# Main-v3_0.net
KiCad netlist of a schematic drawn in EAGLE
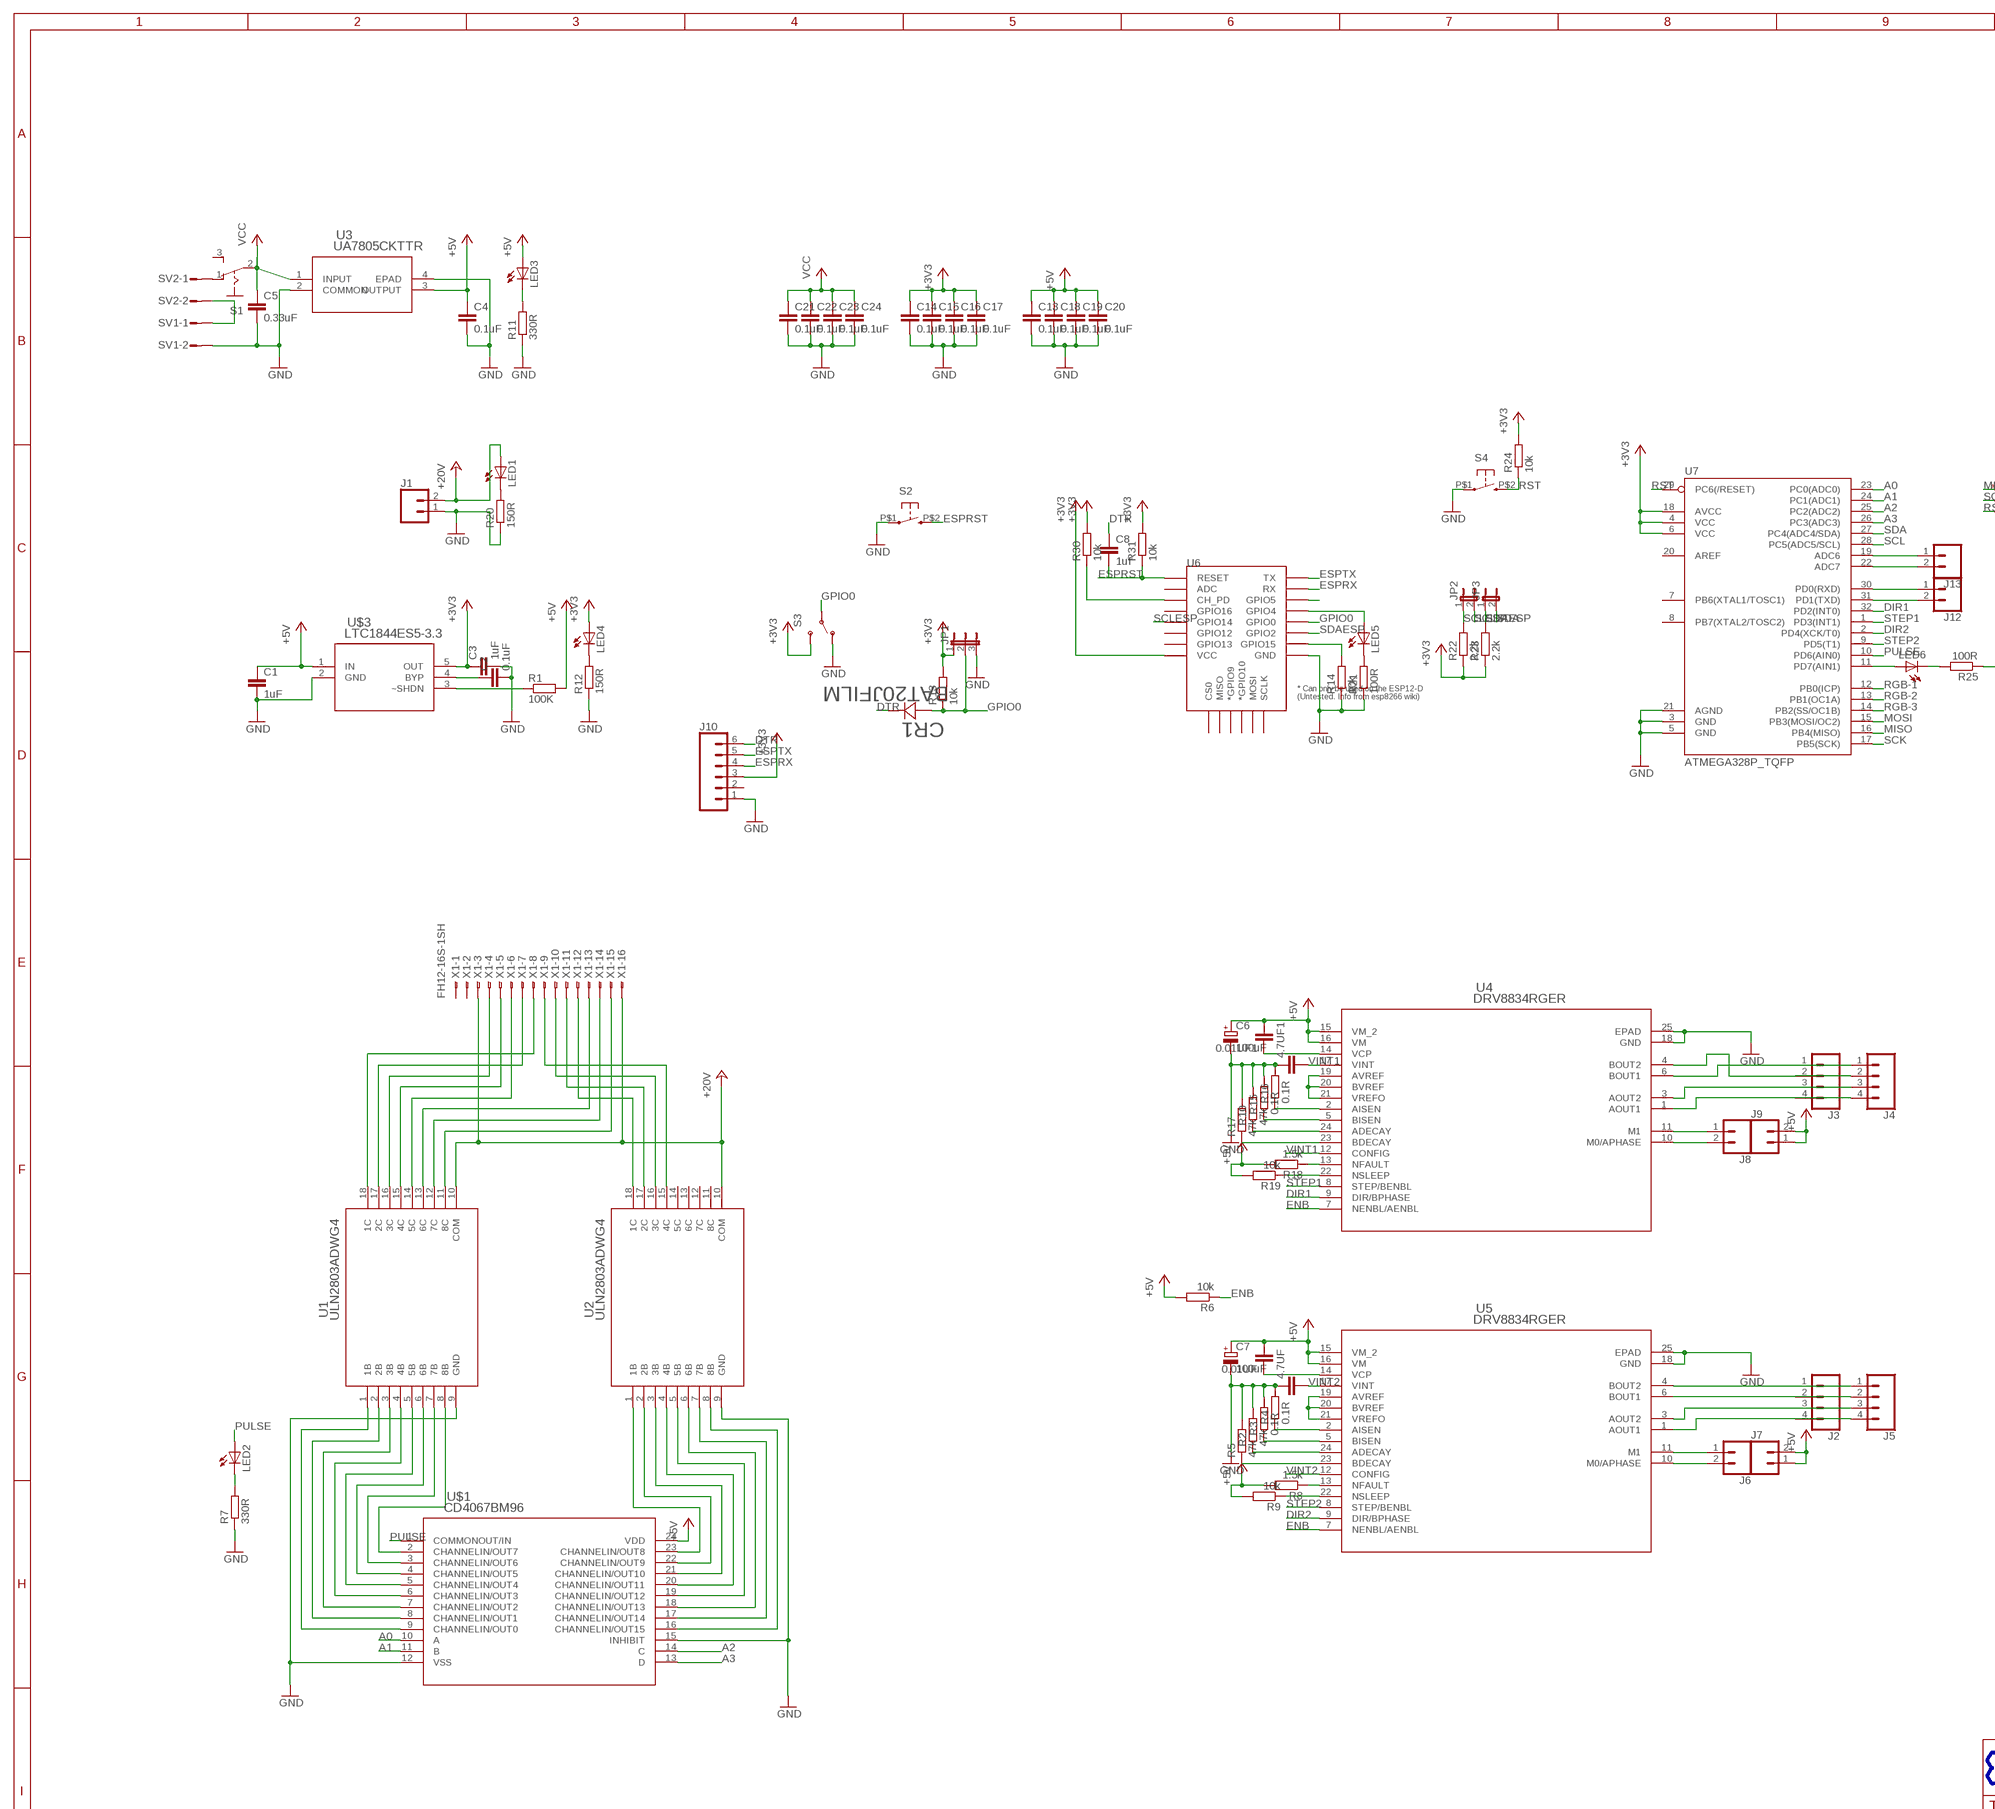
[diagram p0: schematic, sheet 1, part 1 of 2]
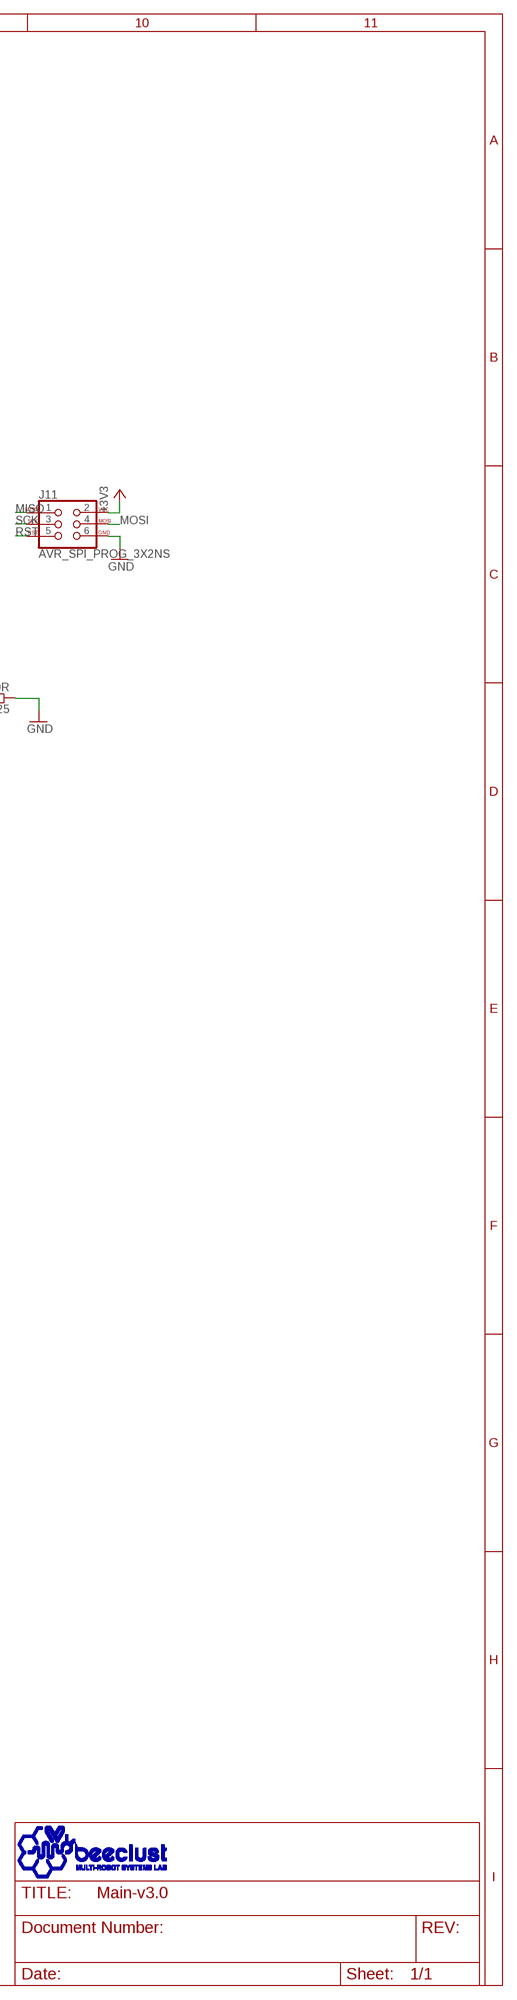
[diagram p1: schematic, sheet 1, part 2 of 2]

(export (version "E")
  (design (tool "Eeschema 10.0.6"))
  (components
    (comp (ref "0.01UF")
      (value "C-EUC0603K")
      (footprint "eagle-import:C0603K")
      (libsource (lib "eagle-import") (part "resistor_348_C-EUC0603K"))
    )
    (comp (ref "0.01UF1")
      (value "C-EUC0603K")
      (footprint "eagle-import:C0603K")
      (libsource (lib "eagle-import") (part "resistor_348_C-EUC0603K"))
    )
    (comp (ref "4.7UF")
      (value "C-EUC0603K")
      (footprint "eagle-import:C0603K")
      (libsource (lib "eagle-import") (part "resistor_348_C-EUC0603K"))
    )
    (comp (ref "4.7UF1")
      (value "C-EUC0603K")
      (footprint "eagle-import:C0603K")
      (libsource (lib "eagle-import") (part "resistor_348_C-EUC0603K"))
    )
    (comp (ref "C1")
      (value "1uF")
      (footprint "eagle-import:C0603")
      (libsource (lib "eagle-import") (part "C-EUC0603"))
    )
    (comp (ref "C2")
      (value "0.1uF")
      (footprint "eagle-import:C0603")
      (libsource (lib "eagle-import") (part "C-EUC0603"))
    )
    (comp (ref "C3")
      (value "1uF")
      (footprint "eagle-import:C0603")
      (libsource (lib "eagle-import") (part "C-EUC0603"))
    )
    (comp (ref "C4")
      (value "0.1uF")
      (footprint "eagle-import:C0603")
      (libsource (lib "eagle-import") (part "C-EUC0603"))
    )
    (comp (ref "C5")
      (value "0.33uF")
      (footprint "eagle-import:C0603")
      (libsource (lib "eagle-import") (part "C-EUC0603"))
    )
    (comp (ref "C6")
      (value "100uF")
      (footprint "eagle-import:E5-5")
      (libsource (lib "eagle-import") (part "CPOL-EUE5-5"))
    )
    (comp (ref "C7")
      (value "100uF")
      (footprint "eagle-import:E5-5")
      (libsource (lib "eagle-import") (part "CPOL-EUE5-5"))
    )
    (comp (ref "C8")
      (value "1uf")
      (footprint "eagle-import:C0603")
      (libsource (lib "eagle-import") (part "resistor_348_C-EUC0603"))
    )
    (comp (ref "C13")
      (value "0.1uF")
      (footprint "eagle-import:C0603")
      (libsource (lib "eagle-import") (part "C-EUC0603"))
    )
    (comp (ref "C14")
      (value "0.1uF")
      (footprint "eagle-import:C0603")
      (libsource (lib "eagle-import") (part "C-EUC0603"))
    )
    (comp (ref "C15")
      (value "0.1uF")
      (footprint "eagle-import:C0603")
      (libsource (lib "eagle-import") (part "C-EUC0603"))
    )
    (comp (ref "C16")
      (value "0.1uF")
      (footprint "eagle-import:C0603")
      (libsource (lib "eagle-import") (part "C-EUC0603"))
    )
    (comp (ref "C17")
      (value "0.1uF")
      (footprint "eagle-import:C0603")
      (libsource (lib "eagle-import") (part "C-EUC0603"))
    )
    (comp (ref "C18")
      (value "0.1uF")
      (footprint "eagle-import:C0603")
      (libsource (lib "eagle-import") (part "C-EUC0603"))
    )
    (comp (ref "C19")
      (value "0.1uF")
      (footprint "eagle-import:C0603")
      (libsource (lib "eagle-import") (part "C-EUC0603"))
    )
    (comp (ref "C20")
      (value "0.1uF")
      (footprint "eagle-import:C0603")
      (libsource (lib "eagle-import") (part "C-EUC0603"))
    )
    (comp (ref "C21")
      (value "0.1uF")
      (footprint "eagle-import:C0603")
      (libsource (lib "eagle-import") (part "C-EUC0603"))
    )
    (comp (ref "C22")
      (value "0.1uF")
      (footprint "eagle-import:C0603")
      (libsource (lib "eagle-import") (part "C-EUC0603"))
    )
    (comp (ref "C23")
      (value "0.1uF")
      (footprint "eagle-import:C0603")
      (libsource (lib "eagle-import") (part "C-EUC0603"))
    )
    (comp (ref "C24")
      (value "0.1uF")
      (footprint "eagle-import:C0603")
      (libsource (lib "eagle-import") (part "C-EUC0603"))
    )
    (comp (ref "CR1")
      (value "BAT20JFILM")
      (footprint "eagle-import:SOD-323")
      (libsource (lib "eagle-import") (part "BAT20JFILM"))
    )
    (comp (ref "J1")
      (value "CONN_02")
      (footprint "eagle-import:1X02")
      (libsource (lib "eagle-import") (part "CONN_02"))
    )
    (comp (ref "J2")
      (value "CONN_04")
      (footprint "eagle-import:1X04")
      (libsource (lib "eagle-import") (part "CONN_04"))
    )
    (comp (ref "J3")
      (value "CONN_04")
      (footprint "eagle-import:1X04")
      (libsource (lib "eagle-import") (part "CONN_04"))
    )
    (comp (ref "J4")
      (value "CONN_04")
      (footprint "eagle-import:1X04")
      (libsource (lib "eagle-import") (part "CONN_04"))
    )
    (comp (ref "J5")
      (value "CONN_04")
      (footprint "eagle-import:1X04")
      (libsource (lib "eagle-import") (part "CONN_04"))
    )
    (comp (ref "J6")
      (value "CONN_02")
      (footprint "eagle-import:1X02")
      (libsource (lib "eagle-import") (part "CONN_02"))
    )
    (comp (ref "J7")
      (value "CONN_02")
      (footprint "eagle-import:1X02")
      (libsource (lib "eagle-import") (part "CONN_02"))
    )
    (comp (ref "J8")
      (value "CONN_02")
      (footprint "eagle-import:1X02")
      (libsource (lib "eagle-import") (part "CONN_02"))
    )
    (comp (ref "J9")
      (value "CONN_02")
      (footprint "eagle-import:1X02")
      (libsource (lib "eagle-import") (part "CONN_02"))
    )
    (comp (ref "J10")
      (value "CONN_06NO_SILK_NO_POP")
      (footprint "eagle-import:1X06_NO_SILK")
      (libsource (lib "eagle-import") (part "CONN_06NO_SILK_NO_POP"))
    )
    (comp (ref "J11")
      (value "AVR_SPI_PROG_3X2NS")
      (footprint "eagle-import:2X3-NS")
      (libsource (lib "eagle-import") (part "AVR_SPI_PROG_3X2NS"))
    )
    (comp (ref "J12")
      (value "CONN_02")
      (footprint "eagle-import:1X02")
      (libsource (lib "eagle-import") (part "CONN_02"))
    )
    (comp (ref "J13")
      (value "CONN_02")
      (footprint "eagle-import:1X02")
      (libsource (lib "eagle-import") (part "CONN_02"))
    )
    (comp (ref "JP1")
      (value "JP2E")
      (footprint "eagle-import:JP2")
      (libsource (lib "eagle-import") (part "JP2E"))
    )
    (comp (ref "JP2")
      (value "JP1E")
      (footprint "eagle-import:JP1")
      (libsource (lib "eagle-import") (part "JP1E"))
    )
    (comp (ref "JP3")
      (value "JP1E")
      (footprint "eagle-import:JP1")
      (libsource (lib "eagle-import") (part "JP1E"))
    )
    (comp (ref "LED1")
      (value "LEDSML0603")
      (footprint "eagle-import:SML0603")
      (libsource (lib "eagle-import") (part "LEDSML0603"))
    )
    (comp (ref "LED2")
      (value "LEDSML0603")
      (footprint "eagle-import:SML0603")
      (libsource (lib "eagle-import") (part "LEDSML0603"))
    )
    (comp (ref "LED3")
      (value "LEDSML0603")
      (footprint "eagle-import:SML0603")
      (libsource (lib "eagle-import") (part "LEDSML0603"))
    )
    (comp (ref "LED4")
      (value "LEDSML0603")
      (footprint "eagle-import:SML0603")
      (libsource (lib "eagle-import") (part "LEDSML0603"))
    )
    (comp (ref "LED5")
      (value "LEDSML0603")
      (footprint "eagle-import:SML0603")
      (libsource (lib "eagle-import") (part "LEDSML0603"))
    )
    (comp (ref "LED6")
      (value "LEDSML0603")
      (footprint "eagle-import:SML0603")
      (libsource (lib "eagle-import") (part "LEDSML0603"))
    )
    (comp (ref "R1")
      (value "100K")
      (footprint "eagle-import:R0603")
      (libsource (lib "eagle-import") (part "R-EU_R0603"))
    )
    (comp (ref "R2")
      (value "47k")
      (footprint "eagle-import:R0402")
      (libsource (lib "eagle-import") (part "resistor_348_R-EU_R0402"))
    )
    (comp (ref "R3")
      (value "0.1R")
      (footprint "eagle-import:R0402")
      (libsource (lib "eagle-import") (part "resistor_348_R-EU_R0402"))
    )
    (comp (ref "R4")
      (value "0.1R")
      (footprint "eagle-import:R0402")
      (libsource (lib "eagle-import") (part "resistor_348_R-EU_R0402"))
    )
    (comp (ref "R5")
      (value "47k")
      (footprint "eagle-import:R0402")
      (libsource (lib "eagle-import") (part "resistor_348_R-EU_R0402"))
    )
    (comp (ref "R6")
      (value "10k")
      (footprint "eagle-import:R0402")
      (libsource (lib "eagle-import") (part "resistor_348_R-EU_R0402"))
    )
    (comp (ref "R7")
      (value "330R")
      (footprint "eagle-import:R0603")
      (libsource (lib "eagle-import") (part "R-EU_R0603"))
    )
    (comp (ref "R8")
      (value "1.5k")
      (footprint "eagle-import:R0402")
      (libsource (lib "eagle-import") (part "resistor_348_R-EU_R0402"))
    )
    (comp (ref "R9")
      (value "10k")
      (footprint "eagle-import:R0402")
      (libsource (lib "eagle-import") (part "resistor_348_R-EU_R0402"))
    )
    (comp (ref "R10")
      (value "47k")
      (footprint "eagle-import:R0402")
      (libsource (lib "eagle-import") (part "resistor_348_R-EU_R0402"))
    )
    (comp (ref "R11")
      (value "330R")
      (footprint "eagle-import:R0603")
      (libsource (lib "eagle-import") (part "R-EU_R0603"))
    )
    (comp (ref "R12")
      (value "150R")
      (footprint "eagle-import:R0603")
      (libsource (lib "eagle-import") (part "R-EU_R0603"))
    )
    (comp (ref "R13")
      (value "10k")
      (footprint "eagle-import:R0603")
      (libsource (lib "eagle-import") (part "R-EU_R0603"))
    )
    (comp (ref "R14")
      (value "10k")
      (footprint "eagle-import:R0603")
      (libsource (lib "eagle-import") (part "R-EU_R0603"))
    )
    (comp (ref "R15")
      (value "0.1R")
      (footprint "eagle-import:R0402")
      (libsource (lib "eagle-import") (part "resistor_348_R-EU_R0402"))
    )
    (comp (ref "R16")
      (value "0.1R")
      (footprint "eagle-import:R0402")
      (libsource (lib "eagle-import") (part "resistor_348_R-EU_R0402"))
    )
    (comp (ref "R17")
      (value "47k")
      (footprint "eagle-import:R0402")
      (libsource (lib "eagle-import") (part "resistor_348_R-EU_R0402"))
    )
    (comp (ref "R18")
      (value "1.5k")
      (footprint "eagle-import:R0402")
      (libsource (lib "eagle-import") (part "resistor_348_R-EU_R0402"))
    )
    (comp (ref "R19")
      (value "10k")
      (footprint "eagle-import:R0402")
      (libsource (lib "eagle-import") (part "resistor_348_R-EU_R0402"))
    )
    (comp (ref "R20")
      (value "150R")
      (footprint "eagle-import:R0603")
      (libsource (lib "eagle-import") (part "R-EU_R0603"))
    )
    (comp (ref "R21")
      (value "100R")
      (footprint "eagle-import:R0603")
      (libsource (lib "eagle-import") (part "R-EU_R0603"))
    )
    (comp (ref "R22")
      (value "2.2k")
      (footprint "eagle-import:R0603")
      (libsource (lib "eagle-import") (part "R-EU_R0603"))
    )
    (comp (ref "R23")
      (value "2.2k")
      (footprint "eagle-import:R0603")
      (libsource (lib "eagle-import") (part "R-EU_R0603"))
    )
    (comp (ref "R24")
      (value "10k")
      (footprint "eagle-import:R0603")
      (libsource (lib "eagle-import") (part "R-EU_R0603"))
    )
    (comp (ref "R25")
      (value "100R")
      (footprint "eagle-import:R0603")
      (libsource (lib "eagle-import") (part "R-EU_R0603"))
    )
    (comp (ref "R30")
      (value "10k")
      (footprint "eagle-import:R0603")
      (libsource (lib "eagle-import") (part "R-EU_R0603"))
    )
    (comp (ref "R31")
      (value "10k")
      (footprint "eagle-import:R0603")
      (libsource (lib "eagle-import") (part "R-EU_R0603"))
    )
    (comp (ref "S1")
      (value "255SB")
      (footprint "eagle-import:255SB")
      (libsource (lib "eagle-import") (part "255SB"))
    )
    (comp (ref "S2")
      (value "KSS")
      (footprint "eagle-import:KSS")
      (libsource (lib "eagle-import") (part "KSS"))
    )
    (comp (ref "S3")
      (value "SWITCH-SPDT-SMD-A")
      (footprint "eagle-import:SWITCH-SPST-SMD-A")
      (libsource (lib "eagle-import") (part "SWITCH-SPDT-SMD-A"))
    )
    (comp (ref "S4")
      (value "KSS")
      (footprint "eagle-import:KSS")
      (libsource (lib "eagle-import") (part "KSS"))
    )
    (comp (ref "SV1")
      (value "L02P")
      (footprint "eagle-import:L02P")
      (libsource (lib "eagle-import") (part "L02P"))
    )
    (comp (ref "SV2")
      (value "L02P")
      (footprint "eagle-import:L02P")
      (libsource (lib "eagle-import") (part "L02P"))
    )
    (comp (ref "U$1")
      (value "CD4067BM96")
      (footprint "eagle-import:DW24")
      (fields (field (name "MANUFACTURER_PART_NUMBER") "CD4067B_DW_24"))
      (libsource (lib "eagle-import") (part "CD4067BM96"))
    )
    (comp (ref "U$2")
      (value "BEECLUST-LOGO")
      (footprint "eagle-import:LOGO")
      (libsource (lib "eagle-import") (part "BEECLUST-LOGO"))
    )
    (comp (ref "U$3")
      (value "LTC1844ES5-3.3")
      (footprint "eagle-import:TSOT-23_S5")
      (libsource (lib "eagle-import") (part "LTC1844ES5-3.3"))
    )
    (comp (ref "U1")
      (value "ULN2803ADWG4")
      (footprint "eagle-import:DW18")
      (libsource (lib "eagle-import") (part "ULN2803ADWG4"))
    )
    (comp (ref "U2")
      (value "ULN2803ADWG4")
      (footprint "eagle-import:DW18")
      (libsource (lib "eagle-import") (part "ULN2803ADWG4"))
    )
    (comp (ref "U3")
      (value "UA7805CKTTR")
      (footprint "eagle-import:KTT3_6P22X6P6")
      (libsource (lib "eagle-import") (part "UA7805CKTTR"))
    )
    (comp (ref "U4")
      (value "DRV8834RGER")
      (footprint "eagle-import:RGE24_2P45X2P45")
      (libsource (lib "eagle-import") (part "DRV8834RGER"))
    )
    (comp (ref "U5")
      (value "DRV8834RGER")
      (footprint "eagle-import:RGE24_2P45X2P45")
      (libsource (lib "eagle-import") (part "DRV8834RGER"))
    )
    (comp (ref "U6")
      (value "ESP12ESMD")
      (footprint "eagle-import:ESP12E-SMD")
      (libsource (lib "eagle-import") (part "ESP12ESMD"))
    )
    (comp (ref "U7")
      (value "ATMEGA328P_TQFP")
      (footprint "eagle-import:TQFP32-08")
      (libsource (lib "eagle-import") (part "ATMEGA328P_TQFP"))
    )
    (comp (ref "X1")
      (value "FH12-16S-1SH")
      (footprint "eagle-import:FH12-16S-1SH")
      (libsource (lib "eagle-import") (part "FH12-16S-1SH"))
    )
  )
  (nets
    (net (code "1") (name "+3V3") (class "Default")
      (node (ref "C14") (pin "1") (pinfunction "1_1") (pintype "passive"))
      (node (ref "C15") (pin "1") (pinfunction "1_1") (pintype "passive"))
      (node (ref "C16") (pin "1") (pinfunction "1_1") (pintype "passive"))
      (node (ref "C17") (pin "1") (pinfunction "1_1") (pintype "passive"))
      (node (ref "C3") (pin "1") (pinfunction "1_1") (pintype "passive"))
      (node (ref "J10") (pin "3") (pinfunction "3_3") (pintype "passive"))
      (node (ref "J11") (pin "2") (pinfunction "2_2") (pintype "passive"))
      (node (ref "JP1") (pin "1") (pinfunction "1_1") (pintype "passive"))
      (node (ref "LED4") (pin "A") (pinfunction "A_A") (pintype "passive"))
      (node (ref "R13") (pin "2") (pinfunction "2_2") (pintype "passive"))
      (node (ref "R22") (pin "1") (pinfunction "1_1") (pintype "passive"))
      (node (ref "R23") (pin "1") (pinfunction "1_1") (pintype "passive"))
      (node (ref "R24") (pin "2") (pinfunction "2_2") (pintype "passive"))
      (node (ref "R30") (pin "2") (pinfunction "2_2") (pintype "passive"))
      (node (ref "R31") (pin "2") (pinfunction "2_2") (pintype "passive"))
      (node (ref "S3") (pin "3") (pinfunction "S_3") (pintype "passive"))
      (node (ref "U$3") (pin "5") (pinfunction "OUT_5") (pintype "passive"))
      (node (ref "U6") (pin "VCC") (pinfunction "VCC_VCC") (pintype "bidirectional"))
      (node (ref "U7") (pin "18") (pinfunction "AVCC_18") (pintype "bidirectional"))
      (node (ref "U7") (pin "4") (pinfunction "VCC_4") (pintype "bidirectional"))
      (node (ref "U7") (pin "6") (pinfunction "VCC_6") (pintype "bidirectional"))
    )
    (net (code "2") (name "+5V") (class "Default")
      (node (ref "0.01UF") (pin "2") (pinfunction "2_2") (pintype "passive"))
      (node (ref "0.01UF1") (pin "2") (pinfunction "2_2") (pintype "passive"))
      (node (ref "C1") (pin "1") (pinfunction "1_1") (pintype "passive"))
      (node (ref "C13") (pin "1") (pinfunction "1_1") (pintype "passive"))
      (node (ref "C18") (pin "1") (pinfunction "1_1") (pintype "passive"))
      (node (ref "C19") (pin "1") (pinfunction "1_1") (pintype "passive"))
      (node (ref "C20") (pin "1") (pinfunction "1_1") (pintype "passive"))
      (node (ref "C4") (pin "1") (pinfunction "1_1") (pintype "passive"))
      (node (ref "C6") (pin "+") (pinfunction "+_+") (pintype "passive"))
      (node (ref "C7") (pin "+") (pinfunction "+_+") (pintype "passive"))
      (node (ref "J7") (pin "1") (pinfunction "1_1") (pintype "passive"))
      (node (ref "J7") (pin "2") (pinfunction "2_2") (pintype "passive"))
      (node (ref "J9") (pin "1") (pinfunction "1_1") (pintype "passive"))
      (node (ref "J9") (pin "2") (pinfunction "2_2") (pintype "passive"))
      (node (ref "LED3") (pin "A") (pinfunction "A_A") (pintype "passive"))
      (node (ref "R1") (pin "2") (pinfunction "2_2") (pintype "passive"))
      (node (ref "R18") (pin "2") (pinfunction "2_2") (pintype "passive"))
      (node (ref "R19") (pin "2") (pinfunction "2_2") (pintype "passive"))
      (node (ref "R6") (pin "2") (pinfunction "2_2") (pintype "passive"))
      (node (ref "R8") (pin "2") (pinfunction "2_2") (pintype "passive"))
      (node (ref "R9") (pin "2") (pinfunction "2_2") (pintype "passive"))
      (node (ref "U$1") (pin "24") (pinfunction "VDD_24") (pintype "power_in"))
      (node (ref "U$3") (pin "1") (pinfunction "IN_1") (pintype "passive"))
      (node (ref "U3") (pin "3") (pinfunction "OUTPUT_3") (pintype "output"))
      (node (ref "U4") (pin "15") (pinfunction "VM_2_15") (pintype "power_in"))
      (node (ref "U4") (pin "16") (pinfunction "VM_16") (pintype "power_in"))
      (node (ref "U5") (pin "15") (pinfunction "VM_2_15") (pintype "power_in"))
      (node (ref "U5") (pin "16") (pinfunction "VM_16") (pintype "power_in"))
    )
    (net (code "3") (name "+20V") (class "Default")
      (node (ref "J1") (pin "2") (pinfunction "2_2") (pintype "passive"))
      (node (ref "LED1") (pin "A") (pinfunction "A_A") (pintype "passive"))
      (node (ref "U1") (pin "10") (pinfunction "COM_10") (pintype "passive"))
      (node (ref "U2") (pin "10") (pinfunction "COM_10") (pintype "passive"))
      (node (ref "X1") (pin "16") (pinfunction "1_16") (pintype "passive"))
      (node (ref "X1") (pin "3") (pinfunction "1_3") (pintype "passive"))
    )
    (net (code "4") (name "/A0") (class "Default")
      (node (ref "U$1") (pin "10") (pinfunction "A_10") (pintype "passive"))
      (node (ref "U7") (pin "23") (pinfunction "PC0(ADC0)_23") (pintype "bidirectional"))
    )
    (net (code "5") (name "/A1") (class "Default")
      (node (ref "U$1") (pin "11") (pinfunction "B_11") (pintype "passive"))
      (node (ref "U7") (pin "24") (pinfunction "PC1(ADC1)_24") (pintype "bidirectional"))
    )
    (net (code "6") (name "/A2") (class "Default")
      (node (ref "U$1") (pin "14") (pinfunction "C_14") (pintype "passive"))
      (node (ref "U7") (pin "25") (pinfunction "PC2(ADC2)_25") (pintype "bidirectional"))
    )
    (net (code "7") (name "/A3") (class "Default")
      (node (ref "U$1") (pin "13") (pinfunction "D_13") (pintype "passive"))
      (node (ref "U7") (pin "26") (pinfunction "PC3(ADC3)_26") (pintype "bidirectional"))
    )
    (net (code "8") (name "/DIR1") (class "Default")
      (node (ref "U4") (pin "9") (pinfunction "DIR/BPHASE_9") (pintype "input"))
      (node (ref "U7") (pin "32") (pinfunction "PD2(INT0)_32") (pintype "bidirectional"))
    )
    (net (code "9") (name "/DIR2") (class "Default")
      (node (ref "U5") (pin "9") (pinfunction "DIR/BPHASE_9") (pintype "input"))
      (node (ref "U7") (pin "2") (pinfunction "PD4(XCK/T0)_2") (pintype "bidirectional"))
    )
    (net (code "10") (name "/DTR") (class "Default")
      (node (ref "C8") (pin "1") (pinfunction "1_1") (pintype "passive"))
      (node (ref "CR1") (pin "1") (pinfunction "11_1") (pintype "passive"))
      (node (ref "J10") (pin "6") (pinfunction "6_6") (pintype "passive"))
    )
    (net (code "11") (name "/ENB") (class "Default")
      (node (ref "R6") (pin "1") (pinfunction "1_1") (pintype "passive"))
      (node (ref "U4") (pin "7") (pinfunction "NENBL/AENBL_7") (pintype "input"))
      (node (ref "U5") (pin "7") (pinfunction "NENBL/AENBL_7") (pintype "input"))
    )
    (net (code "12") (name "/ESPRST") (class "Default")
      (node (ref "C8") (pin "2") (pinfunction "2_2") (pintype "passive"))
      (node (ref "R31") (pin "1") (pinfunction "1_1") (pintype "passive"))
      (node (ref "S2") (pin "P$2") (pinfunction "3_P$2") (pintype "passive"))
      (node (ref "U6") (pin "RESET") (pinfunction "RESET_RESET") (pintype "bidirectional"))
    )
    (net (code "13") (name "/ESPRX") (class "Default")
      (node (ref "J10") (pin "4") (pinfunction "4_4") (pintype "passive"))
      (node (ref "U6") (pin "RXD0") (pinfunction "RX_RXD0") (pintype "bidirectional"))
    )
    (net (code "14") (name "/ESPTX") (class "Default")
      (node (ref "J10") (pin "5") (pinfunction "5_5") (pintype "passive"))
      (node (ref "U6") (pin "TXD0") (pinfunction "TX_TXD0") (pintype "bidirectional"))
    )
    (net (code "15") (name "/GPIO0") (class "Default")
      (node (ref "CR1") (pin "2") (pinfunction "22_2") (pintype "passive"))
      (node (ref "JP1") (pin "2") (pinfunction "2_2") (pintype "passive"))
      (node (ref "R13") (pin "1") (pinfunction "1_1") (pintype "passive"))
      (node (ref "S3") (pin "2") (pinfunction "P_2") (pintype "passive"))
      (node (ref "U6") (pin "GPIO0") (pinfunction "GPIO0_GPIO0") (pintype "bidirectional"))
    )
    (net (code "16") (name "/MISO") (class "Default")
      (node (ref "J11") (pin "1") (pinfunction "1_1") (pintype "passive"))
      (node (ref "U7") (pin "16") (pinfunction "PB4(MISO)_16") (pintype "bidirectional"))
    )
    (net (code "17") (name "/MOSI") (class "Default")
      (node (ref "J11") (pin "4") (pinfunction "4_4") (pintype "passive"))
      (node (ref "U7") (pin "15") (pinfunction "PB3(MOSI/OC2)_15") (pintype "bidirectional"))
    )
    (net (code "18") (name "/PULSE") (class "Default")
      (node (ref "LED2") (pin "A") (pinfunction "A_A") (pintype "passive"))
      (node (ref "U$1") (pin "1") (pinfunction "COMMONOUT/IN_1") (pintype "bidirectional"))
      (node (ref "U7") (pin "10") (pinfunction "PD6(AIN0)_10") (pintype "bidirectional"))
    )
    (net (code "19") (name "/RGB-1") (class "Default")
      (node (ref "U7") (pin "12") (pinfunction "PB0(ICP)_12") (pintype "bidirectional"))
    )
    (net (code "20") (name "/RGB-2") (class "Default")
      (node (ref "U7") (pin "13") (pinfunction "PB1(OC1A)_13") (pintype "bidirectional"))
    )
    (net (code "21") (name "/RGB-3") (class "Default")
      (node (ref "U7") (pin "14") (pinfunction "PB2(SS/OC1B)_14") (pintype "bidirectional"))
    )
    (net (code "22") (name "/RST") (class "Default")
      (node (ref "J11") (pin "5") (pinfunction "5_5") (pintype "passive"))
      (node (ref "R24") (pin "1") (pinfunction "1_1") (pintype "passive"))
      (node (ref "S4") (pin "P$2") (pinfunction "3_P$2") (pintype "passive"))
      (node (ref "U7") (pin "29") (pinfunction "PC6(/RESET)_29") (pintype "bidirectional"))
    )
    (net (code "23") (name "/SCK") (class "Default")
      (node (ref "J11") (pin "3") (pinfunction "3_3") (pintype "passive"))
      (node (ref "U7") (pin "17") (pinfunction "PB5(SCK)_17") (pintype "bidirectional"))
    )
    (net (code "24") (name "/SCL") (class "Default")
      (node (ref "JP2") (pin "2") (pinfunction "2_2") (pintype "passive"))
      (node (ref "U7") (pin "28") (pinfunction "PC5(ADC5/SCL)_28") (pintype "bidirectional"))
    )
    (net (code "25") (name "/SCLESP") (class "Default")
      (node (ref "JP2") (pin "1") (pinfunction "1_1") (pintype "passive"))
      (node (ref "R22") (pin "2") (pinfunction "2_2") (pintype "passive"))
      (node (ref "U6") (pin "GPIO14") (pinfunction "GPIO14_GPIO14") (pintype "bidirectional"))
    )
    (net (code "26") (name "/SDA") (class "Default")
      (node (ref "JP3") (pin "2") (pinfunction "2_2") (pintype "passive"))
      (node (ref "U7") (pin "27") (pinfunction "PC4(ADC4/SDA)_27") (pintype "bidirectional"))
    )
    (net (code "27") (name "/SDAESP") (class "Default")
      (node (ref "JP3") (pin "1") (pinfunction "1_1") (pintype "passive"))
      (node (ref "R23") (pin "2") (pinfunction "2_2") (pintype "passive"))
      (node (ref "U6") (pin "GPIO2") (pinfunction "GPIO2_GPIO2") (pintype "bidirectional"))
    )
    (net (code "28") (name "/STEP1") (class "Default")
      (node (ref "U4") (pin "8") (pinfunction "STEP/BENBL_8") (pintype "input"))
      (node (ref "U7") (pin "1") (pinfunction "PD3(INT1)_1") (pintype "bidirectional"))
    )
    (net (code "29") (name "/STEP2") (class "Default")
      (node (ref "U5") (pin "8") (pinfunction "STEP/BENBL_8") (pintype "input"))
      (node (ref "U7") (pin "9") (pinfunction "PD5(T1)_9") (pintype "bidirectional"))
    )
    (net (code "30") (name "/VINT1") (class "Default")
      (node (ref "4.7UF1") (pin "2") (pinfunction "2_2") (pintype "passive"))
      (node (ref "U4") (pin "12") (pinfunction "CONFIG_12") (pintype "input"))
      (node (ref "U4") (pin "17") (pinfunction "VINT_17") (pintype "passive"))
    )
    (net (code "31") (name "/VINT2") (class "Default")
      (node (ref "4.7UF") (pin "2") (pinfunction "2_2") (pintype "passive"))
      (node (ref "U5") (pin "12") (pinfunction "CONFIG_12") (pintype "input"))
      (node (ref "U5") (pin "17") (pinfunction "VINT_17") (pintype "passive"))
    )
    (net (code "32") (name "GND") (class "Default")
      (node (ref "4.7UF") (pin "1") (pinfunction "1_1") (pintype "passive"))
      (node (ref "4.7UF1") (pin "1") (pinfunction "1_1") (pintype "passive"))
      (node (ref "C1") (pin "2") (pinfunction "2_2") (pintype "passive"))
      (node (ref "C13") (pin "2") (pinfunction "2_2") (pintype "passive"))
      (node (ref "C14") (pin "2") (pinfunction "2_2") (pintype "passive"))
      (node (ref "C15") (pin "2") (pinfunction "2_2") (pintype "passive"))
      (node (ref "C16") (pin "2") (pinfunction "2_2") (pintype "passive"))
      (node (ref "C17") (pin "2") (pinfunction "2_2") (pintype "passive"))
      (node (ref "C18") (pin "2") (pinfunction "2_2") (pintype "passive"))
      (node (ref "C19") (pin "2") (pinfunction "2_2") (pintype "passive"))
      (node (ref "C2") (pin "2") (pinfunction "2_2") (pintype "passive"))
      (node (ref "C20") (pin "2") (pinfunction "2_2") (pintype "passive"))
      (node (ref "C21") (pin "2") (pinfunction "2_2") (pintype "passive"))
      (node (ref "C22") (pin "2") (pinfunction "2_2") (pintype "passive"))
      (node (ref "C23") (pin "2") (pinfunction "2_2") (pintype "passive"))
      (node (ref "C24") (pin "2") (pinfunction "2_2") (pintype "passive"))
      (node (ref "C3") (pin "2") (pinfunction "2_2") (pintype "passive"))
      (node (ref "C4") (pin "2") (pinfunction "2_2") (pintype "passive"))
      (node (ref "C5") (pin "2") (pinfunction "2_2") (pintype "passive"))
      (node (ref "C6") (pin "-") (pinfunction "-_-") (pintype "passive"))
      (node (ref "C7") (pin "-") (pinfunction "-_-") (pintype "passive"))
      (node (ref "J1") (pin "1") (pinfunction "1_1") (pintype "passive"))
      (node (ref "J10") (pin "1") (pinfunction "1_1") (pintype "passive"))
      (node (ref "J11") (pin "6") (pinfunction "6_6") (pintype "passive"))
      (node (ref "JP1") (pin "3") (pinfunction "3_3") (pintype "passive"))
      (node (ref "R10") (pin "2") (pinfunction "2_2") (pintype "passive"))
      (node (ref "R11") (pin "1") (pinfunction "1_1") (pintype "passive"))
      (node (ref "R12") (pin "1") (pinfunction "1_1") (pintype "passive"))
      (node (ref "R14") (pin "1") (pinfunction "1_1") (pintype "passive"))
      (node (ref "R15") (pin "2") (pinfunction "2_2") (pintype "passive"))
      (node (ref "R16") (pin "2") (pinfunction "2_2") (pintype "passive"))
      (node (ref "R17") (pin "2") (pinfunction "2_2") (pintype "passive"))
      (node (ref "R2") (pin "2") (pinfunction "2_2") (pintype "passive"))
      (node (ref "R20") (pin "1") (pinfunction "1_1") (pintype "passive"))
      (node (ref "R21") (pin "1") (pinfunction "1_1") (pintype "passive"))
      (node (ref "R25") (pin "1") (pinfunction "1_1") (pintype "passive"))
      (node (ref "R3") (pin "2") (pinfunction "2_2") (pintype "passive"))
      (node (ref "R4") (pin "2") (pinfunction "2_2") (pintype "passive"))
      (node (ref "R5") (pin "2") (pinfunction "2_2") (pintype "passive"))
      (node (ref "R7") (pin "1") (pinfunction "1_1") (pintype "passive"))
      (node (ref "S2") (pin "P$1") (pinfunction "1_P$1") (pintype "passive"))
      (node (ref "S3") (pin "1") (pinfunction "O_1") (pintype "passive"))
      (node (ref "S4") (pin "P$1") (pinfunction "1_P$1") (pintype "passive"))
      (node (ref "SV1") (pin "2") (pinfunction "S_2") (pintype "passive"))
      (node (ref "U$1") (pin "12") (pinfunction "VSS_12") (pintype "power_in"))
      (node (ref "U$1") (pin "15") (pinfunction "INHIBIT_15") (pintype "passive"))
      (node (ref "U$3") (pin "2") (pinfunction "GND_2") (pintype "passive"))
      (node (ref "U1") (pin "9") (pinfunction "GND_9") (pintype "passive"))
      (node (ref "U2") (pin "9") (pinfunction "GND_9") (pintype "passive"))
      (node (ref "U3") (pin "2") (pinfunction "COMMON_2") (pintype "power_in"))
      (node (ref "U3") (pin "4") (pinfunction "EPAD_4") (pintype "passive"))
      (node (ref "U4") (pin "18") (pinfunction "GND_18") (pintype "power_in"))
      (node (ref "U4") (pin "25") (pinfunction "EPAD_25") (pintype "passive"))
      (node (ref "U5") (pin "18") (pinfunction "GND_18") (pintype "power_in"))
      (node (ref "U5") (pin "25") (pinfunction "EPAD_25") (pintype "passive"))
      (node (ref "U6") (pin "GND") (pinfunction "GND_GND") (pintype "bidirectional"))
      (node (ref "U7") (pin "21") (pinfunction "AGND_21") (pintype "bidirectional"))
      (node (ref "U7") (pin "3") (pinfunction "GND_3") (pintype "bidirectional"))
      (node (ref "U7") (pin "5") (pinfunction "GND_5") (pintype "bidirectional"))
    )
    (net (code "33") (name "Net-(LED1-PadC)") (class "Default")
      (node (ref "LED1") (pin "C") (pinfunction "C_C") (pintype "passive"))
      (node (ref "R20") (pin "2") (pinfunction "2_2") (pintype "passive"))
    )
    (net (code "34") (name "Net-(LED2-PadC)") (class "Default")
      (node (ref "LED2") (pin "C") (pinfunction "C_C") (pintype "passive"))
      (node (ref "R7") (pin "2") (pinfunction "2_2") (pintype "passive"))
    )
    (net (code "35") (name "Net-(LED3-PadC)") (class "Default")
      (node (ref "LED3") (pin "C") (pinfunction "C_C") (pintype "passive"))
      (node (ref "R11") (pin "2") (pinfunction "2_2") (pintype "passive"))
    )
    (net (code "36") (name "Net-(LED4-PadC)") (class "Default")
      (node (ref "LED4") (pin "C") (pinfunction "C_C") (pintype "passive"))
      (node (ref "R12") (pin "2") (pinfunction "2_2") (pintype "passive"))
    )
    (net (code "37") (name "Net-(LED5-PadA)") (class "Default")
      (node (ref "LED5") (pin "A") (pinfunction "A_A") (pintype "passive"))
      (node (ref "U6") (pin "GPIO4") (pinfunction "GPIO4_GPIO4") (pintype "bidirectional"))
    )
    (net (code "38") (name "Net-(LED5-PadC)") (class "Default")
      (node (ref "LED5") (pin "C") (pinfunction "C_C") (pintype "passive"))
      (node (ref "R21") (pin "2") (pinfunction "2_2") (pintype "passive"))
    )
    (net (code "39") (name "Net-(LED6-PadC)") (class "Default")
      (node (ref "LED6") (pin "C") (pinfunction "C_C") (pintype "passive"))
      (node (ref "R25") (pin "2") (pinfunction "2_2") (pintype "passive"))
    )
    (net (code "40") (name "Net-(R14-Pad2)") (class "Default")
      (node (ref "R14") (pin "2") (pinfunction "2_2") (pintype "passive"))
      (node (ref "U6") (pin "GPIO15") (pinfunction "GPIO15_GPIO15") (pintype "bidirectional"))
    )
    (net (code "41") (name "Net-(R30-Pad1)") (class "Default")
      (node (ref "R30") (pin "1") (pinfunction "1_1") (pintype "passive"))
      (node (ref "U6") (pin "CH_PD") (pinfunction "CH_PD_CH_PD") (pintype "bidirectional"))
    )
    (net (code "42") (name "Net-(S1-O)") (class "Default")
      (node (ref "S1") (pin "1") (pinfunction "O_1") (pintype "passive"))
      (node (ref "SV2") (pin "1") (pinfunction "S_1") (pintype "passive"))
    )
    (net (code "43") (name "Net-(SV1A-S)") (class "Default")
      (node (ref "SV1") (pin "1") (pinfunction "S_1") (pintype "passive"))
      (node (ref "SV2") (pin "2") (pinfunction "S_2") (pintype "passive"))
    )
    (net (code "44") (name "Net-(U$1-CHANNELIN{slash}OUT0)") (class "Default")
      (node (ref "U$1") (pin "9") (pinfunction "CHANNELIN/OUT0_9") (pintype "bidirectional"))
      (node (ref "U1") (pin "1") (pinfunction "1B_1") (pintype "passive"))
    )
    (net (code "45") (name "Net-(U$1-CHANNELIN{slash}OUT1)") (class "Default")
      (node (ref "U$1") (pin "8") (pinfunction "CHANNELIN/OUT1_8") (pintype "bidirectional"))
      (node (ref "U1") (pin "2") (pinfunction "2B_2") (pintype "passive"))
    )
    (net (code "46") (name "Net-(U$1-CHANNELIN{slash}OUT2)") (class "Default")
      (node (ref "U$1") (pin "7") (pinfunction "CHANNELIN/OUT2_7") (pintype "bidirectional"))
      (node (ref "U1") (pin "3") (pinfunction "3B_3") (pintype "passive"))
    )
    (net (code "47") (name "Net-(U$1-CHANNELIN{slash}OUT3)") (class "Default")
      (node (ref "U$1") (pin "6") (pinfunction "CHANNELIN/OUT3_6") (pintype "bidirectional"))
      (node (ref "U1") (pin "4") (pinfunction "4B_4") (pintype "passive"))
    )
    (net (code "48") (name "Net-(U$1-CHANNELIN{slash}OUT4)") (class "Default")
      (node (ref "U$1") (pin "5") (pinfunction "CHANNELIN/OUT4_5") (pintype "bidirectional"))
      (node (ref "U1") (pin "5") (pinfunction "5B_5") (pintype "passive"))
    )
    (net (code "49") (name "Net-(U$1-CHANNELIN{slash}OUT5)") (class "Default")
      (node (ref "U$1") (pin "4") (pinfunction "CHANNELIN/OUT5_4") (pintype "bidirectional"))
      (node (ref "U1") (pin "6") (pinfunction "6B_6") (pintype "passive"))
    )
    (net (code "50") (name "Net-(U$1-CHANNELIN{slash}OUT6)") (class "Default")
      (node (ref "U$1") (pin "3") (pinfunction "CHANNELIN/OUT6_3") (pintype "bidirectional"))
      (node (ref "U1") (pin "7") (pinfunction "7B_7") (pintype "passive"))
    )
    (net (code "51") (name "Net-(U$1-CHANNELIN{slash}OUT7)") (class "Default")
      (node (ref "U$1") (pin "2") (pinfunction "CHANNELIN/OUT7_2") (pintype "bidirectional"))
      (node (ref "U1") (pin "8") (pinfunction "8B_8") (pintype "passive"))
    )
    (net (code "52") (name "Net-(U$1-CHANNELIN{slash}OUT8)") (class "Default")
      (node (ref "U$1") (pin "23") (pinfunction "CHANNELIN/OUT8_23") (pintype "bidirectional"))
      (node (ref "U2") (pin "1") (pinfunction "1B_1") (pintype "passive"))
    )
    (net (code "53") (name "Net-(U$1-CHANNELIN{slash}OUT9)") (class "Default")
      (node (ref "U$1") (pin "22") (pinfunction "CHANNELIN/OUT9_22") (pintype "bidirectional"))
      (node (ref "U2") (pin "2") (pinfunction "2B_2") (pintype "passive"))
    )
    (net (code "54") (name "Net-(U$1-CHANNELIN{slash}OUT10)") (class "Default")
      (node (ref "U$1") (pin "21") (pinfunction "CHANNELIN/OUT10_21") (pintype "bidirectional"))
      (node (ref "U2") (pin "3") (pinfunction "3B_3") (pintype "passive"))
    )
    (net (code "55") (name "Net-(U$1-CHANNELIN{slash}OUT11)") (class "Default")
      (node (ref "U$1") (pin "20") (pinfunction "CHANNELIN/OUT11_20") (pintype "bidirectional"))
      (node (ref "U2") (pin "4") (pinfunction "4B_4") (pintype "passive"))
    )
    (net (code "56") (name "Net-(U$1-CHANNELIN{slash}OUT12)") (class "Default")
      (node (ref "U$1") (pin "19") (pinfunction "CHANNELIN/OUT12_19") (pintype "bidirectional"))
      (node (ref "U2") (pin "5") (pinfunction "5B_5") (pintype "passive"))
    )
    (net (code "57") (name "Net-(U$1-CHANNELIN{slash}OUT13)") (class "Default")
      (node (ref "U$1") (pin "18") (pinfunction "CHANNELIN/OUT13_18") (pintype "bidirectional"))
      (node (ref "U2") (pin "6") (pinfunction "6B_6") (pintype "passive"))
    )
    (net (code "58") (name "Net-(U$1-CHANNELIN{slash}OUT14)") (class "Default")
      (node (ref "U$1") (pin "17") (pinfunction "CHANNELIN/OUT14_17") (pintype "bidirectional"))
      (node (ref "U2") (pin "7") (pinfunction "7B_7") (pintype "passive"))
    )
    (net (code "59") (name "Net-(U$1-CHANNELIN{slash}OUT15)") (class "Default")
      (node (ref "U$1") (pin "16") (pinfunction "CHANNELIN/OUT15_16") (pintype "bidirectional"))
      (node (ref "U2") (pin "8") (pinfunction "8B_8") (pintype "passive"))
    )
    (net (code "60") (name "Net-(U$3-BYP)") (class "Default")
      (node (ref "C2") (pin "1") (pinfunction "1_1") (pintype "passive"))
      (node (ref "U$3") (pin "4") (pinfunction "BYP_4") (pintype "passive"))
    )
    (net (code "61") (name "Net-(U$3-~{SHDN})") (class "Default")
      (node (ref "R1") (pin "1") (pinfunction "1_1") (pintype "passive"))
      (node (ref "U$3") (pin "3") (pinfunction "~{SHDN}_3") (pintype "passive"))
    )
    (net (code "62") (name "Net-(U1-1C)") (class "Default")
      (node (ref "U1") (pin "18") (pinfunction "1C_18") (pintype "passive"))
      (node (ref "X1") (pin "8") (pinfunction "1_8") (pintype "passive"))
    )
    (net (code "63") (name "Net-(U1-2C)") (class "Default")
      (node (ref "U1") (pin "17") (pinfunction "2C_17") (pintype "passive"))
      (node (ref "X1") (pin "7") (pinfunction "1_7") (pintype "passive"))
    )
    (net (code "64") (name "Net-(U1-3C)") (class "Default")
      (node (ref "U1") (pin "16") (pinfunction "3C_16") (pintype "passive"))
      (node (ref "X1") (pin "4") (pinfunction "1_4") (pintype "passive"))
    )
    (net (code "65") (name "Net-(U1-4C)") (class "Default")
      (node (ref "U1") (pin "15") (pinfunction "4C_15") (pintype "passive"))
      (node (ref "X1") (pin "5") (pinfunction "1_5") (pintype "passive"))
    )
    (net (code "66") (name "Net-(U1-5C)") (class "Default")
      (node (ref "U1") (pin "14") (pinfunction "5C_14") (pintype "passive"))
      (node (ref "X1") (pin "6") (pinfunction "1_6") (pintype "passive"))
    )
    (net (code "67") (name "Net-(U1-6C)") (class "Default")
      (node (ref "U1") (pin "13") (pinfunction "6C_13") (pintype "passive"))
      (node (ref "X1") (pin "13") (pinfunction "1_13") (pintype "passive"))
    )
    (net (code "68") (name "Net-(U1-7C)") (class "Default")
      (node (ref "U1") (pin "12") (pinfunction "7C_12") (pintype "passive"))
      (node (ref "X1") (pin "14") (pinfunction "1_14") (pintype "passive"))
    )
    (net (code "69") (name "Net-(U1-8C)") (class "Default")
      (node (ref "U1") (pin "11") (pinfunction "8C_11") (pintype "passive"))
      (node (ref "X1") (pin "15") (pinfunction "1_15") (pintype "passive"))
    )
    (net (code "70") (name "Net-(U2-1C)") (class "Default")
      (node (ref "U2") (pin "18") (pinfunction "1C_18") (pintype "passive"))
      (node (ref "X1") (pin "12") (pinfunction "1_12") (pintype "passive"))
    )
    (net (code "71") (name "Net-(U2-2C)") (class "Default")
      (node (ref "U2") (pin "17") (pinfunction "2C_17") (pintype "passive"))
      (node (ref "X1") (pin "11") (pinfunction "1_11") (pintype "passive"))
    )
    (net (code "72") (name "Net-(U2-3C)") (class "Default")
      (node (ref "U2") (pin "16") (pinfunction "3C_16") (pintype "passive"))
      (node (ref "X1") (pin "10") (pinfunction "1_10") (pintype "passive"))
    )
    (net (code "73") (name "Net-(U2-4C)") (class "Default")
      (node (ref "U2") (pin "15") (pinfunction "4C_15") (pintype "passive"))
      (node (ref "X1") (pin "9") (pinfunction "1_9") (pintype "passive"))
    )
    (net (code "74") (name "Net-(U4-ADECAY)") (class "Default")
      (node (ref "R10") (pin "1") (pinfunction "1_1") (pintype "passive"))
      (node (ref "U4") (pin "24") (pinfunction "ADECAY_24") (pintype "input"))
    )
    (net (code "75") (name "Net-(U4-AISEN)") (class "Default")
      (node (ref "R16") (pin "1") (pinfunction "1_1") (pintype "passive"))
      (node (ref "U4") (pin "2") (pinfunction "AISEN_2") (pintype "bidirectional"))
    )
    (net (code "76") (name "Net-(U4-AOUT1)") (class "Default")
      (node (ref "J3") (pin "4") (pinfunction "4_4") (pintype "passive"))
      (node (ref "J4") (pin "4") (pinfunction "4_4") (pintype "passive"))
      (node (ref "U4") (pin "1") (pinfunction "AOUT1_1") (pintype "output"))
    )
    (net (code "77") (name "Net-(U4-AOUT2)") (class "Default")
      (node (ref "J3") (pin "3") (pinfunction "3_3") (pintype "passive"))
      (node (ref "J4") (pin "3") (pinfunction "3_3") (pintype "passive"))
      (node (ref "U4") (pin "3") (pinfunction "AOUT2_3") (pintype "output"))
    )
    (net (code "78") (name "Net-(U4-AVREF)") (class "Default")
      (node (ref "U4") (pin "19") (pinfunction "AVREF_19") (pintype "input"))
      (node (ref "U4") (pin "20") (pinfunction "BVREF_20") (pintype "input"))
      (node (ref "U4") (pin "21") (pinfunction "VREFO_21") (pintype "output"))
    )
    (net (code "79") (name "Net-(U4-BDECAY)") (class "Default")
      (node (ref "R17") (pin "1") (pinfunction "1_1") (pintype "passive"))
      (node (ref "U4") (pin "23") (pinfunction "BDECAY_23") (pintype "input"))
    )
    (net (code "80") (name "Net-(U4-BISEN)") (class "Default")
      (node (ref "R15") (pin "1") (pinfunction "1_1") (pintype "passive"))
      (node (ref "U4") (pin "5") (pinfunction "BISEN_5") (pintype "bidirectional"))
    )
    (net (code "81") (name "Net-(U4-BOUT1)") (class "Default")
      (node (ref "J3") (pin "1") (pinfunction "1_1") (pintype "passive"))
      (node (ref "J4") (pin "1") (pinfunction "1_1") (pintype "passive"))
      (node (ref "U4") (pin "6") (pinfunction "BOUT1_6") (pintype "output"))
    )
    (net (code "82") (name "Net-(U4-BOUT2)") (class "Default")
      (node (ref "J3") (pin "2") (pinfunction "2_2") (pintype "passive"))
      (node (ref "J4") (pin "2") (pinfunction "2_2") (pintype "passive"))
      (node (ref "U4") (pin "4") (pinfunction "BOUT2_4") (pintype "output"))
    )
    (net (code "83") (name "Net-(U4-M0{slash}APHASE)") (class "Default")
      (node (ref "J8") (pin "2") (pinfunction "2_2") (pintype "passive"))
      (node (ref "U4") (pin "10") (pinfunction "M0/APHASE_10") (pintype "input"))
    )
    (net (code "84") (name "Net-(U4-M1)") (class "Default")
      (node (ref "J8") (pin "1") (pinfunction "1_1") (pintype "passive"))
      (node (ref "U4") (pin "11") (pinfunction "M1_11") (pintype "input"))
    )
    (net (code "85") (name "Net-(U4-NFAULT)") (class "Default")
      (node (ref "R18") (pin "1") (pinfunction "1_1") (pintype "passive"))
      (node (ref "U4") (pin "13") (pinfunction "NFAULT_13") (pintype "output"))
    )
    (net (code "86") (name "Net-(U4-NSLEEP)") (class "Default")
      (node (ref "R19") (pin "1") (pinfunction "1_1") (pintype "passive"))
      (node (ref "U4") (pin "22") (pinfunction "NSLEEP_22") (pintype "input"))
    )
    (net (code "87") (name "Net-(U4-VCP)") (class "Default")
      (node (ref "0.01UF1") (pin "1") (pinfunction "1_1") (pintype "passive"))
      (node (ref "U4") (pin "14") (pinfunction "VCP_14") (pintype "output"))
    )
    (net (code "88") (name "Net-(U5-ADECAY)") (class "Default")
      (node (ref "R2") (pin "1") (pinfunction "1_1") (pintype "passive"))
      (node (ref "U5") (pin "24") (pinfunction "ADECAY_24") (pintype "input"))
    )
    (net (code "89") (name "Net-(U5-AISEN)") (class "Default")
      (node (ref "R4") (pin "1") (pinfunction "1_1") (pintype "passive"))
      (node (ref "U5") (pin "2") (pinfunction "AISEN_2") (pintype "bidirectional"))
    )
    (net (code "90") (name "Net-(U5-AOUT1)") (class "Default")
      (node (ref "J2") (pin "4") (pinfunction "4_4") (pintype "passive"))
      (node (ref "J5") (pin "4") (pinfunction "4_4") (pintype "passive"))
      (node (ref "U5") (pin "1") (pinfunction "AOUT1_1") (pintype "output"))
    )
    (net (code "91") (name "Net-(U5-AOUT2)") (class "Default")
      (node (ref "J2") (pin "3") (pinfunction "3_3") (pintype "passive"))
      (node (ref "J5") (pin "3") (pinfunction "3_3") (pintype "passive"))
      (node (ref "U5") (pin "3") (pinfunction "AOUT2_3") (pintype "output"))
    )
    (net (code "92") (name "Net-(U5-AVREF)") (class "Default")
      (node (ref "U5") (pin "19") (pinfunction "AVREF_19") (pintype "input"))
      (node (ref "U5") (pin "20") (pinfunction "BVREF_20") (pintype "input"))
      (node (ref "U5") (pin "21") (pinfunction "VREFO_21") (pintype "output"))
    )
    (net (code "93") (name "Net-(U5-BDECAY)") (class "Default")
      (node (ref "R5") (pin "1") (pinfunction "1_1") (pintype "passive"))
      (node (ref "U5") (pin "23") (pinfunction "BDECAY_23") (pintype "input"))
    )
    (net (code "94") (name "Net-(U5-BISEN)") (class "Default")
      (node (ref "R3") (pin "1") (pinfunction "1_1") (pintype "passive"))
      (node (ref "U5") (pin "5") (pinfunction "BISEN_5") (pintype "bidirectional"))
    )
    (net (code "95") (name "Net-(U5-BOUT1)") (class "Default")
      (node (ref "J2") (pin "2") (pinfunction "2_2") (pintype "passive"))
      (node (ref "J5") (pin "2") (pinfunction "2_2") (pintype "passive"))
      (node (ref "U5") (pin "6") (pinfunction "BOUT1_6") (pintype "output"))
    )
    (net (code "96") (name "Net-(U5-BOUT2)") (class "Default")
      (node (ref "J2") (pin "1") (pinfunction "1_1") (pintype "passive"))
      (node (ref "J5") (pin "1") (pinfunction "1_1") (pintype "passive"))
      (node (ref "U5") (pin "4") (pinfunction "BOUT2_4") (pintype "output"))
    )
    (net (code "97") (name "Net-(U5-M0{slash}APHASE)") (class "Default")
      (node (ref "J6") (pin "2") (pinfunction "2_2") (pintype "passive"))
      (node (ref "U5") (pin "10") (pinfunction "M0/APHASE_10") (pintype "input"))
    )
    (net (code "98") (name "Net-(U5-M1)") (class "Default")
      (node (ref "J6") (pin "1") (pinfunction "1_1") (pintype "passive"))
      (node (ref "U5") (pin "11") (pinfunction "M1_11") (pintype "input"))
    )
    (net (code "99") (name "Net-(U5-NFAULT)") (class "Default")
      (node (ref "R8") (pin "1") (pinfunction "1_1") (pintype "passive"))
      (node (ref "U5") (pin "13") (pinfunction "NFAULT_13") (pintype "output"))
    )
    (net (code "100") (name "Net-(U5-NSLEEP)") (class "Default")
      (node (ref "R9") (pin "1") (pinfunction "1_1") (pintype "passive"))
      (node (ref "U5") (pin "22") (pinfunction "NSLEEP_22") (pintype "input"))
    )
    (net (code "101") (name "Net-(U5-VCP)") (class "Default")
      (node (ref "0.01UF") (pin "1") (pinfunction "1_1") (pintype "passive"))
      (node (ref "U5") (pin "14") (pinfunction "VCP_14") (pintype "output"))
    )
    (net (code "102") (name "Net-(U7-ADC6)") (class "Default")
      (node (ref "J13") (pin "1") (pinfunction "1_1") (pintype "passive"))
      (node (ref "U7") (pin "19") (pinfunction "ADC6_19") (pintype "bidirectional"))
    )
    (net (code "103") (name "Net-(U7-ADC7)") (class "Default")
      (node (ref "J13") (pin "2") (pinfunction "2_2") (pintype "passive"))
      (node (ref "U7") (pin "22") (pinfunction "ADC7_22") (pintype "bidirectional"))
    )
    (net (code "104") (name "Net-(U7-PD0(RXD))") (class "Default")
      (node (ref "J12") (pin "1") (pinfunction "1_1") (pintype "passive"))
      (node (ref "U7") (pin "30") (pinfunction "PD0(RXD)_30") (pintype "bidirectional"))
    )
    (net (code "105") (name "Net-(U7-PD1(TXD))") (class "Default")
      (node (ref "J12") (pin "2") (pinfunction "2_2") (pintype "passive"))
      (node (ref "U7") (pin "31") (pinfunction "PD1(TXD)_31") (pintype "bidirectional"))
    )
    (net (code "106") (name "Net-(U7-PD7(AIN1))") (class "Default")
      (node (ref "LED6") (pin "A") (pinfunction "A_A") (pintype "passive"))
      (node (ref "U7") (pin "11") (pinfunction "PD7(AIN1)_11") (pintype "bidirectional"))
    )
    (net (code "107") (name "VCC") (class "Default")
      (node (ref "C21") (pin "1") (pinfunction "1_1") (pintype "passive"))
      (node (ref "C22") (pin "1") (pinfunction "1_1") (pintype "passive"))
      (node (ref "C23") (pin "1") (pinfunction "1_1") (pintype "passive"))
      (node (ref "C24") (pin "1") (pinfunction "1_1") (pintype "passive"))
      (node (ref "C5") (pin "1") (pinfunction "1_1") (pintype "passive"))
      (node (ref "S1") (pin "2") (pinfunction "P_2") (pintype "passive"))
      (node (ref "U3") (pin "1") (pinfunction "INPUT_1") (pintype "input"))
    )
    (net (code "108") (name "unconnected-(J10-Pad2)") (class "Default")
      (node (ref "J10") (pin "2") (pinfunction "2_2") (pintype "passive"))
    )
    (net (code "109") (name "unconnected-(S1-S-Pad3)") (class "Default")
      (node (ref "S1") (pin "3") (pinfunction "S_3") (pintype "passive"))
    )
    (net (code "110") (name "unconnected-(U2-5C-Pad14)") (class "Default")
      (node (ref "U2") (pin "14") (pinfunction "5C_14") (pintype "passive"))
    )
    (net (code "111") (name "unconnected-(U2-6C-Pad13)") (class "Default")
      (node (ref "U2") (pin "13") (pinfunction "6C_13") (pintype "passive"))
    )
    (net (code "112") (name "unconnected-(U2-7C-Pad12)") (class "Default")
      (node (ref "U2") (pin "12") (pinfunction "7C_12") (pintype "passive"))
    )
    (net (code "113") (name "unconnected-(U2-8C-Pad11)") (class "Default")
      (node (ref "U2") (pin "11") (pinfunction "8C_11") (pintype "passive"))
    )
    (net (code "114") (name "unconnected-(U6-*GPIO9-PadGPIO9)") (class "Default")
      (node (ref "U6") (pin "GPIO9") (pinfunction "*GPIO9_GPIO9") (pintype "bidirectional"))
    )
    (net (code "115") (name "unconnected-(U6-*GPIO10-PadGPIO10)") (class "Default")
      (node (ref "U6") (pin "GPIO10") (pinfunction "*GPIO10_GPIO10") (pintype "bidirectional"))
    )
    (net (code "116") (name "unconnected-(U6-PadADC)") (class "Default")
      (node (ref "U6") (pin "ADC") (pinfunction "ADC_ADC") (pintype "bidirectional"))
    )
    (net (code "117") (name "unconnected-(U6-PadCS0)") (class "Default")
      (node (ref "U6") (pin "CS0") (pinfunction "CS0_CS0") (pintype "bidirectional"))
    )
    (net (code "118") (name "unconnected-(U6-PadGPIO5)") (class "Default")
      (node (ref "U6") (pin "GPIO5") (pinfunction "GPIO5_GPIO5") (pintype "bidirectional"))
    )
    (net (code "119") (name "unconnected-(U6-PadGPIO12)") (class "Default")
      (node (ref "U6") (pin "GPIO12") (pinfunction "GPIO12_GPIO12") (pintype "bidirectional"))
    )
    (net (code "120") (name "unconnected-(U6-PadGPIO13)") (class "Default")
      (node (ref "U6") (pin "GPIO13") (pinfunction "GPIO13_GPIO13") (pintype "bidirectional"))
    )
    (net (code "121") (name "unconnected-(U6-PadGPIO16)") (class "Default")
      (node (ref "U6") (pin "GPIO16") (pinfunction "GPIO16_GPIO16") (pintype "bidirectional"))
    )
    (net (code "122") (name "unconnected-(U6-PadMISO)") (class "Default")
      (node (ref "U6") (pin "MISO") (pinfunction "MISO_MISO") (pintype "bidirectional"))
    )
    (net (code "123") (name "unconnected-(U6-PadMOSI)") (class "Default")
      (node (ref "U6") (pin "MOSI") (pinfunction "MOSI_MOSI") (pintype "bidirectional"))
    )
    (net (code "124") (name "unconnected-(U6-PadSCLK)") (class "Default")
      (node (ref "U6") (pin "SCLK") (pinfunction "SCLK_SCLK") (pintype "bidirectional"))
    )
    (net (code "125") (name "unconnected-(U7-AREF-Pad20)") (class "Default")
      (node (ref "U7") (pin "20") (pinfunction "AREF_20") (pintype "bidirectional"))
    )
    (net (code "126") (name "unconnected-(U7-PB6(XTAL1{slash}TOSC1)-Pad7)") (class "Default")
      (node (ref "U7") (pin "7") (pinfunction "PB6(XTAL1/TOSC1)_7") (pintype "bidirectional"))
    )
    (net (code "127") (name "unconnected-(U7-PB7(XTAL2{slash}TOSC2)-Pad8)") (class "Default")
      (node (ref "U7") (pin "8") (pinfunction "PB7(XTAL2/TOSC2)_8") (pintype "bidirectional"))
    )
    (net (code "128") (name "unconnected-(X1-Pad1)") (class "Default")
      (node (ref "X1") (pin "1") (pinfunction "1_1") (pintype "passive"))
    )
    (net (code "129") (name "unconnected-(X1I-1-Pad2)") (class "Default")
      (node (ref "X1") (pin "2") (pinfunction "1_2") (pintype "passive"))
    )
  )
)
